# ARDUINO_GPIO.net
KiCad netlist of a schematic drawn in Altium Designer
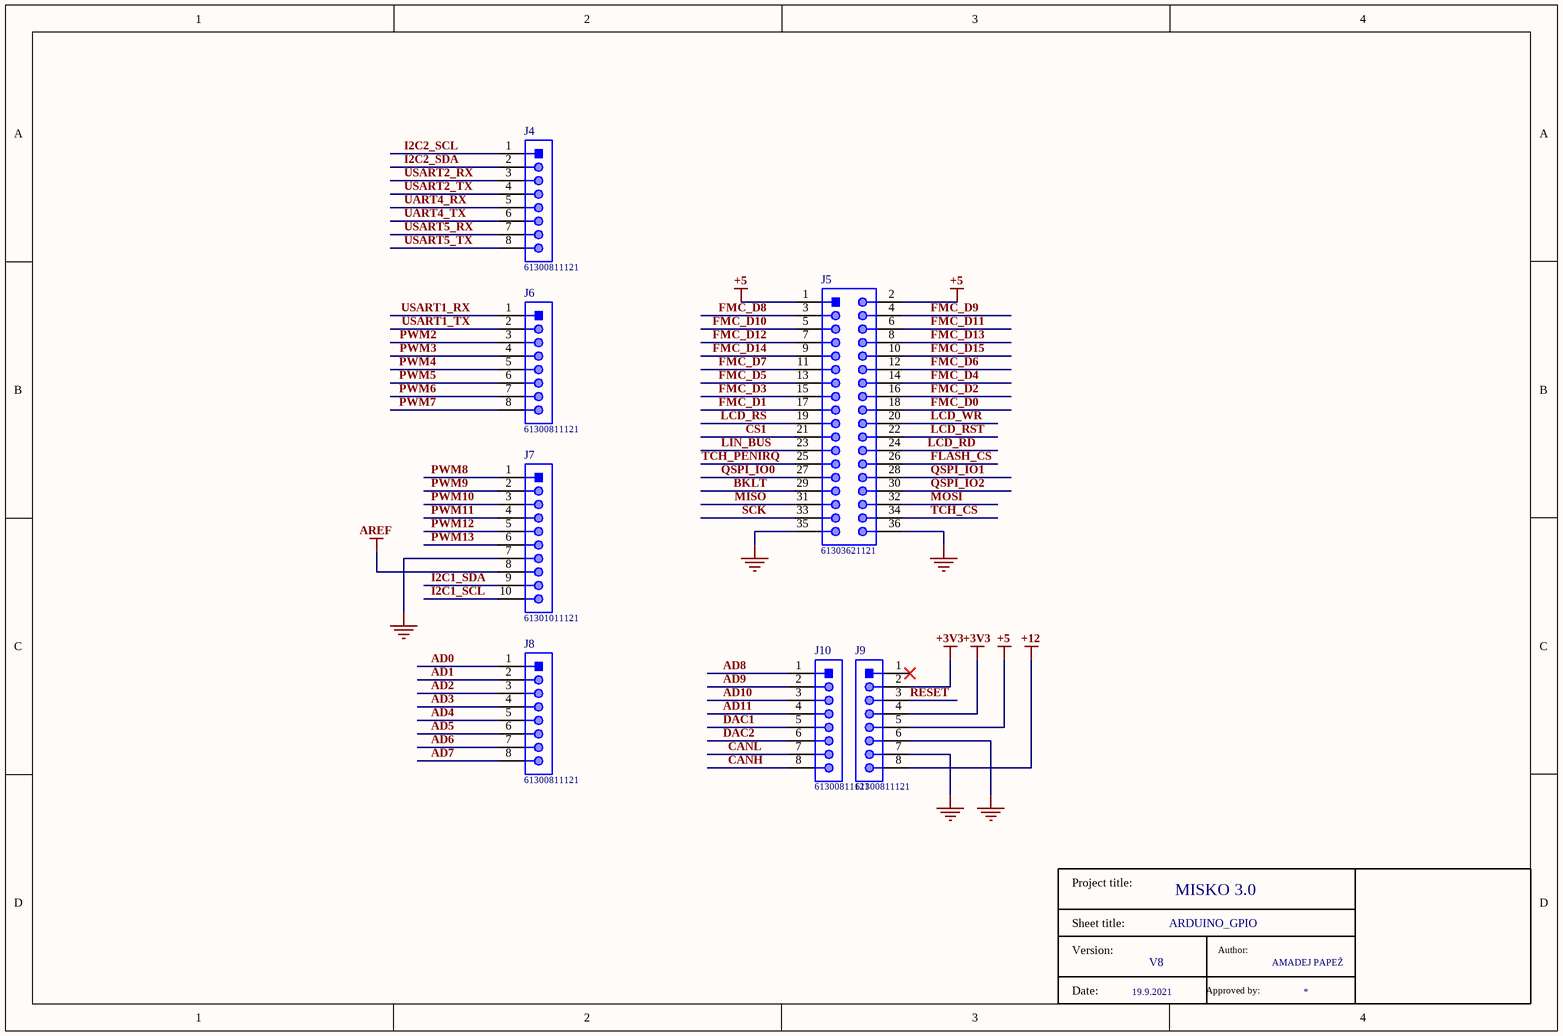
[diagram p0: ARDUINO_GPIO.SchDoc]

(export (version "E")
  (design (tool "Eeschema 10.0.6"))
  (components
    (comp (ref "J4")
      (value "61300811121")
      (footprint "61300811121")
      (description "THT Vertical Pin Header WR-PHD, Pitch 2.54 mm, Single Row, 8 pins")
      (fields (field (name "MANUFACTURER") "Wurth Elektronik") (field (name "PUBLISHER") "WurthElektronik"))
      (libsource (lib "Altium Content Vault") (part "WE-CN-1P-M-R8"))
    )
    (comp (ref "J5")
      (value "61303621121")
      (footprint "61303621121")
      (description "THT Vertical Pin Header WR-PHD, Pitch 2.54 mm, Dual Row, 36 pins")
      (fields (field (name "MANUFACTURER") "Wurth Elektronik") (field (name "PUBLISHER") "WurthElektronik"))
      (libsource (lib "Altium Content Vault") (part "WE-CN-2P-M-R36"))
    )
    (comp (ref "J6")
      (value "61300811121")
      (footprint "61300811121")
      (description "THT Vertical Pin Header WR-PHD, Pitch 2.54 mm, Single Row, 8 pins")
      (fields (field (name "MANUFACTURER") "Wurth Elektronik") (field (name "PUBLISHER") "WurthElektronik"))
      (libsource (lib "Altium Content Vault") (part "WE-CN-1P-M-R8"))
    )
    (comp (ref "J7")
      (value "61301011121")
      (footprint "61301011121")
      (description "THT Vertical Pin Header WR-PHD, Pitch 2.54 mm, Single Row, 10 pins")
      (fields (field (name "MANUFACTURER") "Wurth Elektronik") (field (name "PUBLISHER") "WurthElektronik"))
      (libsource (lib "Altium Content Vault") (part "WE-CN-1P-M-R10"))
    )
    (comp (ref "J8")
      (value "61300811121")
      (footprint "61300811121")
      (description "THT Vertical Pin Header WR-PHD, Pitch 2.54 mm, Single Row, 8 pins")
      (fields (field (name "MANUFACTURER") "Wurth Elektronik") (field (name "PUBLISHER") "WurthElektronik"))
      (libsource (lib "Altium Content Vault") (part "WE-CN-1P-M-R8"))
    )
    (comp (ref "J9")
      (value "61300811121")
      (footprint "61300811121")
      (description "THT Vertical Pin Header WR-PHD, Pitch 2.54 mm, Single Row, 8 pins")
      (fields (field (name "MANUFACTURER") "Wurth Elektronik") (field (name "PUBLISHER") "WurthElektronik"))
      (libsource (lib "") (part "WE-CN-1P-M-R8_1"))
    )
    (comp (ref "J10")
      (value "61300811121")
      (footprint "61300811121")
      (description "THT Vertical Pin Header WR-PHD, Pitch 2.54 mm, Single Row, 8 pins")
      (fields (field (name "MANUFACTURER") "Wurth Elektronik") (field (name "PUBLISHER") "WurthElektronik"))
      (libsource (lib "Altium Content Vault") (part "WE-CN-1P-M-R8"))
    )
    (comp (ref "T6") (value "~") (libsource (lib "MISKO3_V6") (part "Title block")))
  )
  (nets
    (net (code "1") (name "+3V3") (class "Default")
      (node (ref "J9") (pin "2") (pinfunction "2_2") (pintype "passive"))
      (node (ref "J9") (pin "4") (pinfunction "4_4") (pintype "passive"))
    )
    (net (code "2") (name "+5") (class "Default")
      (node (ref "J5") (pin "1") (pinfunction "1_1") (pintype "passive"))
      (node (ref "J5") (pin "2") (pinfunction "2_2") (pintype "passive"))
      (node (ref "J9") (pin "5") (pinfunction "5_5") (pintype "passive"))
    )
    (net (code "3") (name "+12") (class "Default")
      (node (ref "J9") (pin "8") (pinfunction "8_8") (pintype "passive"))
    )
    (net (code "5") (name "/AD0") (class "Default")
      (node (ref "J8") (pin "1") (pinfunction "1_1") (pintype "passive"))
    )
    (net (code "6") (name "/AD1") (class "Default")
      (node (ref "J8") (pin "2") (pinfunction "2_2") (pintype "passive"))
    )
    (net (code "7") (name "/AD2") (class "Default")
      (node (ref "J8") (pin "3") (pinfunction "3_3") (pintype "passive"))
    )
    (net (code "8") (name "/AD3") (class "Default")
      (node (ref "J8") (pin "4") (pinfunction "4_4") (pintype "passive"))
    )
    (net (code "9") (name "/AD4") (class "Default")
      (node (ref "J8") (pin "5") (pinfunction "5_5") (pintype "passive"))
    )
    (net (code "10") (name "/AD5") (class "Default")
      (node (ref "J8") (pin "6") (pinfunction "6_6") (pintype "passive"))
    )
    (net (code "11") (name "/AD6") (class "Default")
      (node (ref "J8") (pin "7") (pinfunction "7_7") (pintype "passive"))
    )
    (net (code "12") (name "/AD7") (class "Default")
      (node (ref "J8") (pin "8") (pinfunction "8_8") (pintype "passive"))
    )
    (net (code "13") (name "/AD8") (class "Default")
      (node (ref "J10") (pin "1") (pinfunction "1_1") (pintype "passive"))
    )
    (net (code "14") (name "/AD9") (class "Default")
      (node (ref "J10") (pin "2") (pinfunction "2_2") (pintype "passive"))
    )
    (net (code "15") (name "/AD10") (class "Default")
      (node (ref "J10") (pin "3") (pinfunction "3_3") (pintype "passive"))
    )
    (net (code "16") (name "/AD11") (class "Default")
      (node (ref "J10") (pin "4") (pinfunction "4_4") (pintype "passive"))
    )
    (net (code "17") (name "/BKLT") (class "Default")
      (node (ref "J5") (pin "29") (pinfunction "29_29") (pintype "passive"))
    )
    (net (code "18") (name "/CANH") (class "Default")
      (node (ref "J10") (pin "8") (pinfunction "8_8") (pintype "passive"))
    )
    (net (code "19") (name "/CANL") (class "Default")
      (node (ref "J10") (pin "7") (pinfunction "7_7") (pintype "passive"))
    )
    (net (code "20") (name "/CS1") (class "Default")
      (node (ref "J5") (pin "21") (pinfunction "21_21") (pintype "passive"))
    )
    (net (code "21") (name "/DAC1") (class "Default")
      (node (ref "J10") (pin "5") (pinfunction "5_5") (pintype "passive"))
    )
    (net (code "22") (name "/DAC2") (class "Default")
      (node (ref "J10") (pin "6") (pinfunction "6_6") (pintype "passive"))
    )
    (net (code "23") (name "/FLASH_CS") (class "Default")
      (node (ref "J5") (pin "26") (pinfunction "26_26") (pintype "passive"))
    )
    (net (code "24") (name "/FMC_D0") (class "Default")
      (node (ref "J5") (pin "18") (pinfunction "18_18") (pintype "passive"))
    )
    (net (code "25") (name "/FMC_D1") (class "Default")
      (node (ref "J5") (pin "17") (pinfunction "17_17") (pintype "passive"))
    )
    (net (code "26") (name "/FMC_D2") (class "Default")
      (node (ref "J5") (pin "16") (pinfunction "16_16") (pintype "passive"))
    )
    (net (code "27") (name "/FMC_D3") (class "Default")
      (node (ref "J5") (pin "15") (pinfunction "15_15") (pintype "passive"))
    )
    (net (code "28") (name "/FMC_D4") (class "Default")
      (node (ref "J5") (pin "14") (pinfunction "14_14") (pintype "passive"))
    )
    (net (code "29") (name "/FMC_D5") (class "Default")
      (node (ref "J5") (pin "13") (pinfunction "13_13") (pintype "passive"))
    )
    (net (code "30") (name "/FMC_D6") (class "Default")
      (node (ref "J5") (pin "12") (pinfunction "12_12") (pintype "passive"))
    )
    (net (code "31") (name "/FMC_D7") (class "Default")
      (node (ref "J5") (pin "11") (pinfunction "11_11") (pintype "passive"))
    )
    (net (code "32") (name "/FMC_D8") (class "Default")
      (node (ref "J5") (pin "3") (pinfunction "3_3") (pintype "passive"))
    )
    (net (code "33") (name "/FMC_D9") (class "Default")
      (node (ref "J5") (pin "4") (pinfunction "4_4") (pintype "passive"))
    )
    (net (code "34") (name "/FMC_D10") (class "Default")
      (node (ref "J5") (pin "5") (pinfunction "5_5") (pintype "passive"))
    )
    (net (code "35") (name "/FMC_D11") (class "Default")
      (node (ref "J5") (pin "6") (pinfunction "6_6") (pintype "passive"))
    )
    (net (code "36") (name "/FMC_D12") (class "Default")
      (node (ref "J5") (pin "7") (pinfunction "7_7") (pintype "passive"))
    )
    (net (code "37") (name "/FMC_D13") (class "Default")
      (node (ref "J5") (pin "8") (pinfunction "8_8") (pintype "passive"))
    )
    (net (code "38") (name "/FMC_D14") (class "Default")
      (node (ref "J5") (pin "9") (pinfunction "9_9") (pintype "passive"))
    )
    (net (code "39") (name "/FMC_D15") (class "Default")
      (node (ref "J5") (pin "10") (pinfunction "10_10") (pintype "passive"))
    )
    (net (code "40") (name "/I2C1_SCL") (class "Default")
      (node (ref "J7") (pin "10") (pinfunction "10_10") (pintype "passive"))
    )
    (net (code "41") (name "/I2C1_SDA") (class "Default")
      (node (ref "J7") (pin "9") (pinfunction "9_9") (pintype "passive"))
    )
    (net (code "42") (name "/I2C2_SCL") (class "Default")
      (node (ref "J4") (pin "1") (pinfunction "1_1") (pintype "passive"))
    )
    (net (code "43") (name "/I2C2_SDA") (class "Default")
      (node (ref "J4") (pin "2") (pinfunction "2_2") (pintype "passive"))
    )
    (net (code "44") (name "/LCD_RD") (class "Default")
      (node (ref "J5") (pin "24") (pinfunction "24_24") (pintype "passive"))
    )
    (net (code "45") (name "/LCD_RS") (class "Default")
      (node (ref "J5") (pin "19") (pinfunction "19_19") (pintype "passive"))
    )
    (net (code "46") (name "/LCD_RST") (class "Default")
      (node (ref "J5") (pin "22") (pinfunction "22_22") (pintype "passive"))
    )
    (net (code "47") (name "/LCD_WR") (class "Default")
      (node (ref "J5") (pin "20") (pinfunction "20_20") (pintype "passive"))
    )
    (net (code "48") (name "/LIN_BUS") (class "Default")
      (node (ref "J5") (pin "23") (pinfunction "23_23") (pintype "passive"))
    )
    (net (code "49") (name "/MISO") (class "Default")
      (node (ref "J5") (pin "31") (pinfunction "31_31") (pintype "passive"))
    )
    (net (code "50") (name "/MOSI") (class "Default")
      (node (ref "J5") (pin "32") (pinfunction "32_32") (pintype "passive"))
    )
    (net (code "51") (name "/PWM2") (class "Default")
      (node (ref "J6") (pin "3") (pinfunction "3_3") (pintype "passive"))
    )
    (net (code "52") (name "/PWM3") (class "Default")
      (node (ref "J6") (pin "4") (pinfunction "4_4") (pintype "passive"))
    )
    (net (code "53") (name "/PWM4") (class "Default")
      (node (ref "J6") (pin "5") (pinfunction "5_5") (pintype "passive"))
    )
    (net (code "54") (name "/PWM5") (class "Default")
      (node (ref "J6") (pin "6") (pinfunction "6_6") (pintype "passive"))
    )
    (net (code "55") (name "/PWM6") (class "Default")
      (node (ref "J6") (pin "7") (pinfunction "7_7") (pintype "passive"))
    )
    (net (code "56") (name "/PWM7") (class "Default")
      (node (ref "J6") (pin "8") (pinfunction "8_8") (pintype "passive"))
    )
    (net (code "57") (name "/PWM8") (class "Default")
      (node (ref "J7") (pin "1") (pinfunction "1_1") (pintype "passive"))
    )
    (net (code "58") (name "/PWM9") (class "Default")
      (node (ref "J7") (pin "2") (pinfunction "2_2") (pintype "passive"))
    )
    (net (code "59") (name "/PWM10") (class "Default")
      (node (ref "J7") (pin "3") (pinfunction "3_3") (pintype "passive"))
    )
    (net (code "60") (name "/PWM11") (class "Default")
      (node (ref "J7") (pin "4") (pinfunction "4_4") (pintype "passive"))
    )
    (net (code "61") (name "/PWM12") (class "Default")
      (node (ref "J7") (pin "5") (pinfunction "5_5") (pintype "passive"))
    )
    (net (code "62") (name "/PWM13") (class "Default")
      (node (ref "J7") (pin "6") (pinfunction "6_6") (pintype "passive"))
    )
    (net (code "63") (name "/QSPI_IO0") (class "Default")
      (node (ref "J5") (pin "27") (pinfunction "27_27") (pintype "passive"))
    )
    (net (code "64") (name "/QSPI_IO1") (class "Default")
      (node (ref "J5") (pin "28") (pinfunction "28_28") (pintype "passive"))
    )
    (net (code "65") (name "/QSPI_IO2") (class "Default")
      (node (ref "J5") (pin "30") (pinfunction "30_30") (pintype "passive"))
    )
    (net (code "66") (name "/RESET") (class "Default")
      (node (ref "J9") (pin "3") (pinfunction "3_3") (pintype "passive"))
    )
    (net (code "67") (name "/SCK") (class "Default")
      (node (ref "J5") (pin "33") (pinfunction "33_33") (pintype "passive"))
    )
    (net (code "68") (name "/TCH_CS") (class "Default")
      (node (ref "J5") (pin "34") (pinfunction "34_34") (pintype "passive"))
    )
    (net (code "69") (name "/TCH_PENIRQ") (class "Default")
      (node (ref "J5") (pin "25") (pinfunction "25_25") (pintype "passive"))
    )
    (net (code "70") (name "/UART4_RX") (class "Default")
      (node (ref "J4") (pin "5") (pinfunction "5_5") (pintype "passive"))
    )
    (net (code "71") (name "/UART4_TX") (class "Default")
      (node (ref "J4") (pin "6") (pinfunction "6_6") (pintype "passive"))
    )
    (net (code "72") (name "/USART1_RX") (class "Default")
      (node (ref "J6") (pin "1") (pinfunction "1_1") (pintype "passive"))
    )
    (net (code "73") (name "/USART1_TX") (class "Default")
      (node (ref "J6") (pin "2") (pinfunction "2_2") (pintype "passive"))
    )
    (net (code "74") (name "/USART2_RX") (class "Default")
      (node (ref "J4") (pin "3") (pinfunction "3_3") (pintype "passive"))
    )
    (net (code "75") (name "/USART2_TX") (class "Default")
      (node (ref "J4") (pin "4") (pinfunction "4_4") (pintype "passive"))
    )
    (net (code "76") (name "/USART5_RX") (class "Default")
      (node (ref "J4") (pin "7") (pinfunction "7_7") (pintype "passive"))
    )
    (net (code "77") (name "/USART5_TX") (class "Default")
      (node (ref "J4") (pin "8") (pinfunction "8_8") (pintype "passive"))
    )
    (net (code "78") (name "AREF") (class "Default")
      (node (ref "J7") (pin "8") (pinfunction "8_8") (pintype "passive"))
    )
    (net (code "79") (name "GND") (class "Default")
      (node (ref "J5") (pin "35") (pinfunction "35_35") (pintype "passive"))
      (node (ref "J5") (pin "36") (pinfunction "36_36") (pintype "passive"))
      (node (ref "J7") (pin "7") (pinfunction "7_7") (pintype "passive"))
      (node (ref "J9") (pin "6") (pinfunction "6_6") (pintype "passive"))
      (node (ref "J9") (pin "7") (pinfunction "7_7") (pintype "passive"))
    )
    (net (code "80") (name "unconnected-(J9-Pad1)") (class "Default")
      (node (ref "J9") (pin "1") (pinfunction "1_1") (pintype "passive+no_connect"))
    )
  )
)
